# USB_power_v1_2025-04-08.net
KiCad netlist of a schematic drawn in EasyEDA Pro
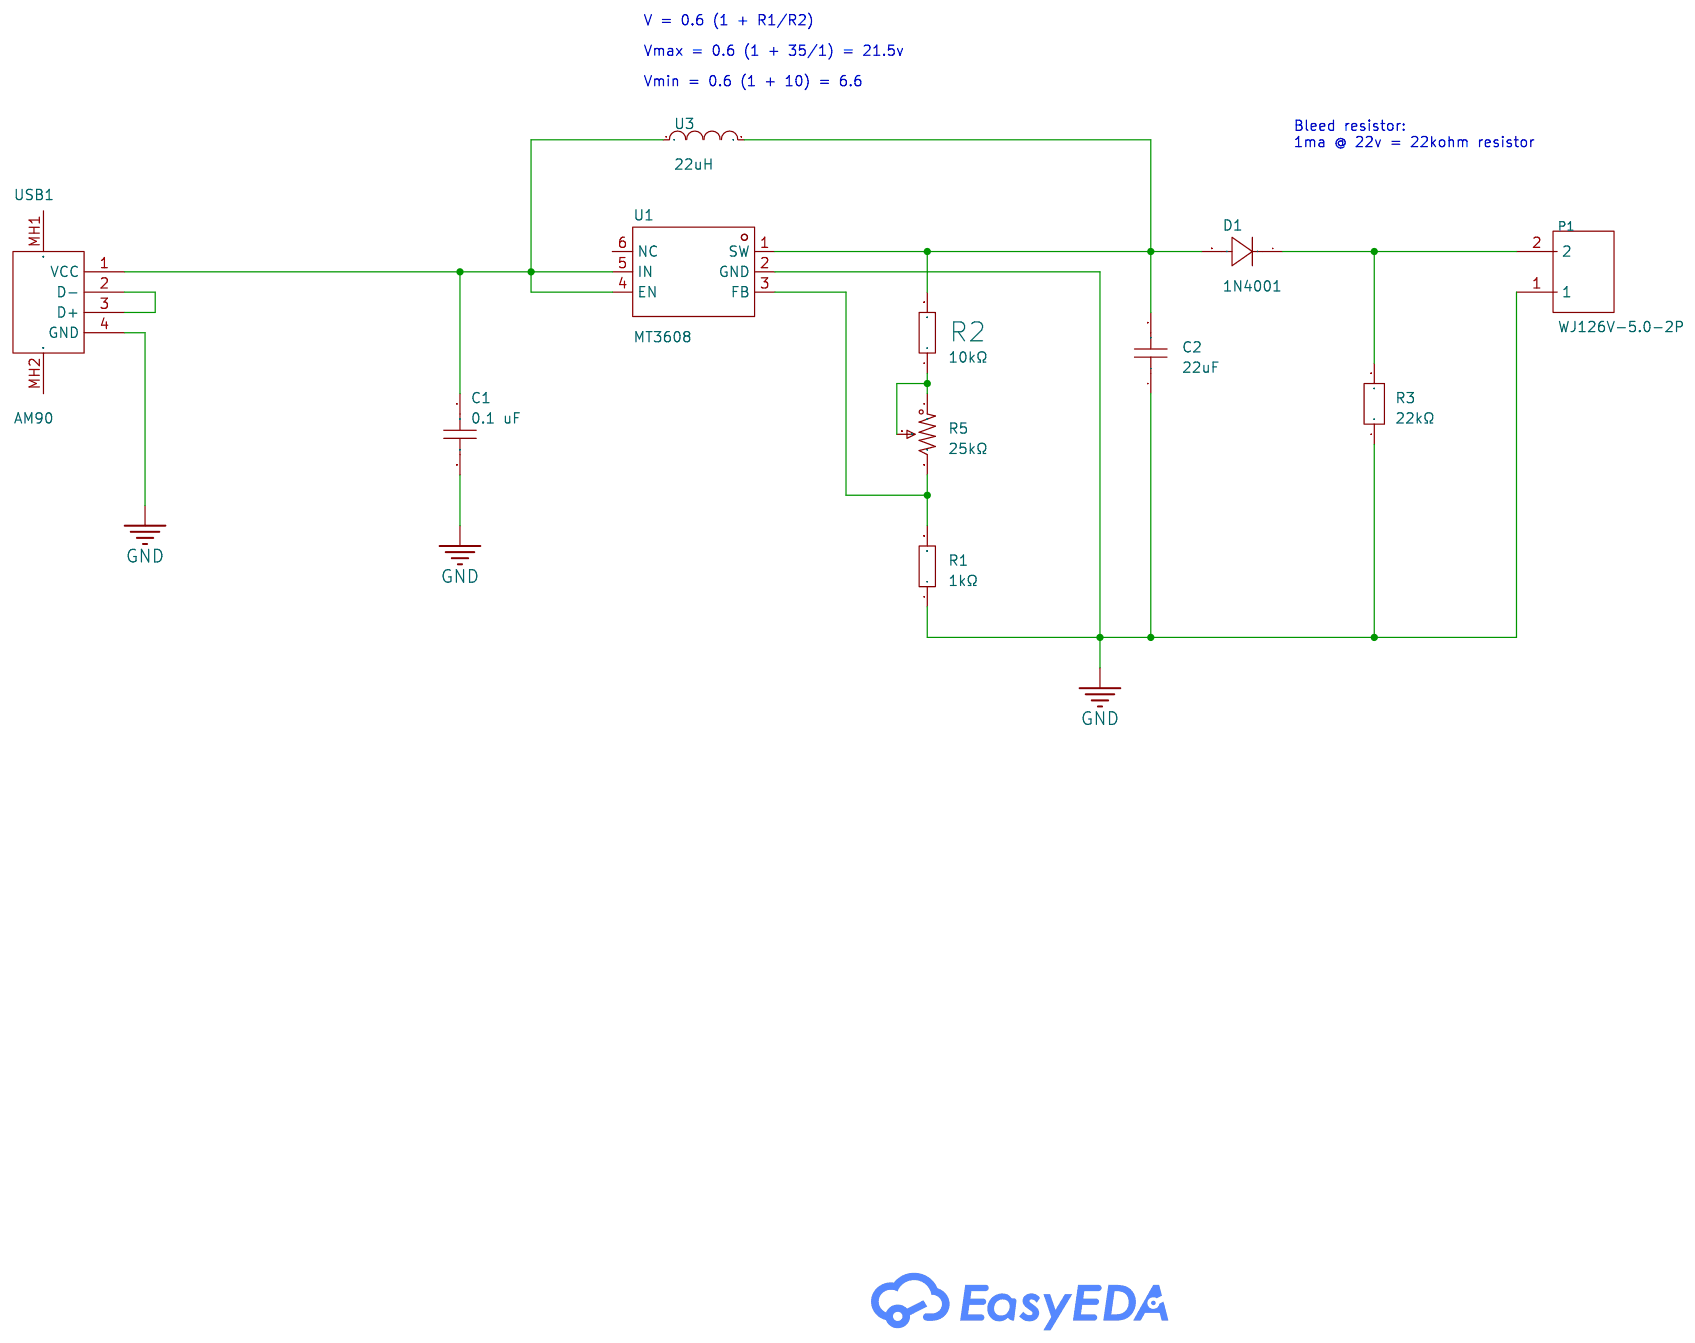
[diagram p0: schematic sheet]

(export (version "E")
  (design (tool "Eeschema 10.0.6"))
  (components
    (comp (ref "C1")
      (value "0.1 uF")
      (footprint "easyedapro:C0603")
      (libsource (lib "easyedapro") (part "CAP"))
    )
    (comp (ref "C2")
      (value "22uF")
      (footprint "easyedapro:C0805")
      (fields
        (field (name "Manufacturer Part") "CL21A226MAQNNNE")
        (field (name "Manufacturer") "SAMSUNG(三星)")
      )
      (libsource (lib "easyedapro") (part "CL21A226MAQNNNE"))
    )
    (comp (ref "D1")
      (value "1N4001")
      (footprint "easyedapro:SOD-123FL_L2.8-W1.8-LS3.7-RD")
      (fields (field (name "Manufacturer") "YONGYUTAI(永裕泰)"))
      (libsource (lib "easyedapro") (part "1N4001_C2892326"))
    )
    (comp (ref "P1")
      (value "WJ126V-5.0-2P")
      (footprint "easyedapro:CONN-TH_WJ126V-5.0-2P")
      (fields (field (name "Manufacturer") "KANGNEX(康奈克斯电气)"))
      (libsource (lib "easyedapro") (part "WJ126V-5.0-2P"))
    )
    (comp (ref "R1")
      (value "1kΩ")
      (footprint "easyedapro:R0603")
      (fields (field (name "Manufacturer Part") "RC0603FR-071KL") (field (name "Manufacturer") "YAGEO(国巨)"))
      (libsource (lib "easyedapro") (part "RC0603FR-071KL"))
    )
    (comp (ref "R2")
      (value "10kΩ")
      (footprint "easyedapro:R0603")
      (fields
        (field (name "Manufacturer Part") "0603WAF1002T5E")
        (field (name "Manufacturer") "UNI-ROYAL(厚声)")
      )
      (libsource (lib "easyedapro") (part "0603WAF1002T5E"))
    )
    (comp (ref "R3")
      (value "22kΩ")
      (footprint "easyedapro:R0603")
      (fields (field (name "Manufacturer Part") "FRC0603F2202TS") (field (name "Manufacturer") "FOJAN(富捷)"))
      (libsource (lib "easyedapro") (part "FRC0603F2202TS"))
    )
    (comp (ref "R5")
      (value "25kΩ")
      (footprint "easyedapro:RES-ADJ-TH_3P-L9.5-W4.85-P2.50-BL-BS")
      (description "Resistance: Tolerance:±10% Tolerance:±10%")
      (fields (field (name "Manufacturer Part") "3296W-1-253") (field (name "Manufacturer") "BOCHEN(博晨)"))
      (libsource (lib "easyedapro") (part "3296W-1-253"))
    )
    (comp (ref "U1")
      (value "MT3608")
      (footprint "easyedapro:SOT-23-6_L2.9-W1.6-P0.95-LS2.8-BL")
      (fields (field (name "Manufacturer") "西安航天民芯"))
      (libsource (lib "easyedapro") (part "MT3608"))
    )
    (comp (ref "U3")
      (value "22uH")
      (footprint "easyedapro:IND-SMD_L7.2-W6.6_GPSR07X0")
      (fields (field (name "Manufacturer Part") "CYA0630-22UH") (field (name "Manufacturer") "SHOU HAN(首韩)"))
      (libsource (lib "easyedapro") (part "CYA0630-22UH"))
    )
    (comp (ref "USB1")
      (value "AM90")
      (footprint "easyedapro:USB-AM-TH_AM90")
      (fields (field (name "Manufacturer") "SHOU HAN(首韩)"))
      (libsource (lib "easyedapro") (part "AM90"))
    )
  )
  (nets
    (net (code "1") (name "GND") (class "Default")
      (node (ref "C1") (pin "2") (pinfunction "2_2") (pintype "input"))
      (node (ref "C2") (pin "1") (pinfunction "1_1") (pintype "unspecified"))
      (node (ref "P1") (pin "1") (pinfunction "1_1") (pintype "input"))
      (node (ref "R1") (pin "1") (pinfunction "1_1") (pintype "input"))
      (node (ref "R3") (pin "1") (pinfunction "1_1") (pintype "unspecified"))
      (node (ref "U1") (pin "2") (pinfunction "GND_2") (pintype "unspecified"))
      (node (ref "USB1") (pin "4") (pinfunction "GND_4") (pintype "input"))
    )
    (net (code "2") (name "Net-(D1-A)") (class "Default")
      (node (ref "C2") (pin "2") (pinfunction "2_2") (pintype "unspecified"))
      (node (ref "D1") (pin "2") (pinfunction "A_2") (pintype "unspecified"))
      (node (ref "R2") (pin "2") (pinfunction "2_2") (pintype "input"))
      (node (ref "U1") (pin "1") (pinfunction "SW_1") (pintype "unspecified"))
      (node (ref "U3") (pin "2") (pinfunction "2_2") (pintype "unspecified"))
    )
    (net (code "3") (name "Net-(D1-K)") (class "Default")
      (node (ref "D1") (pin "1") (pinfunction "K_1") (pintype "unspecified"))
      (node (ref "P1") (pin "2") (pinfunction "2_2") (pintype "input"))
      (node (ref "R3") (pin "2") (pinfunction "2_2") (pintype "unspecified"))
    )
    (net (code "4") (name "Net-(R2-Pad1)") (class "Default")
      (node (ref "R2") (pin "1") (pinfunction "1_1") (pintype "input"))
      (node (ref "R5") (pin "1") (pinfunction "1_1") (pintype "input"))
      (node (ref "R5") (pin "2") (pinfunction "2_2") (pintype "input"))
    )
    (net (code "5") (name "Net-(U1-EN)") (class "Default")
      (node (ref "C1") (pin "1") (pinfunction "1_1") (pintype "input"))
      (node (ref "U1") (pin "4") (pinfunction "EN_4") (pintype "unspecified"))
      (node (ref "U1") (pin "5") (pinfunction "IN_5") (pintype "unspecified"))
      (node (ref "U3") (pin "1") (pinfunction "1_1") (pintype "unspecified"))
      (node (ref "USB1") (pin "1") (pinfunction "VCC_1") (pintype "input"))
    )
    (net (code "6") (name "Net-(U1-FB)") (class "Default")
      (node (ref "R1") (pin "2") (pinfunction "2_2") (pintype "input"))
      (node (ref "R5") (pin "3") (pinfunction "3_3") (pintype "input"))
      (node (ref "U1") (pin "3") (pinfunction "FB_3") (pintype "unspecified"))
    )
    (net (code "7") (name "Net-(USB1-D+)") (class "Default")
      (node (ref "USB1") (pin "2") (pinfunction "D-_2") (pintype "input"))
      (node (ref "USB1") (pin "3") (pinfunction "D+_3") (pintype "input"))
    )
    (net (code "8") (name "unconnected-(U1-NC-Pad6)") (class "Default")
      (node (ref "U1") (pin "6") (pinfunction "NC_6") (pintype "unspecified"))
    )
    (net (code "9") (name "unconnected-(USB1-PadMH1)") (class "Default")
      (node (ref "USB1") (pin "MH1") (pinfunction "MH1_MH1") (pintype "unspecified"))
    )
    (net (code "10") (name "unconnected-(USB1-PadMH2)") (class "Default")
      (node (ref "USB1") (pin "MH2") (pinfunction "MH2_MH2") (pintype "unspecified"))
    )
  )
)
